# MI_04_05_Rev_2_0.net
KiCad netlist of a schematic drawn in Altium Designer
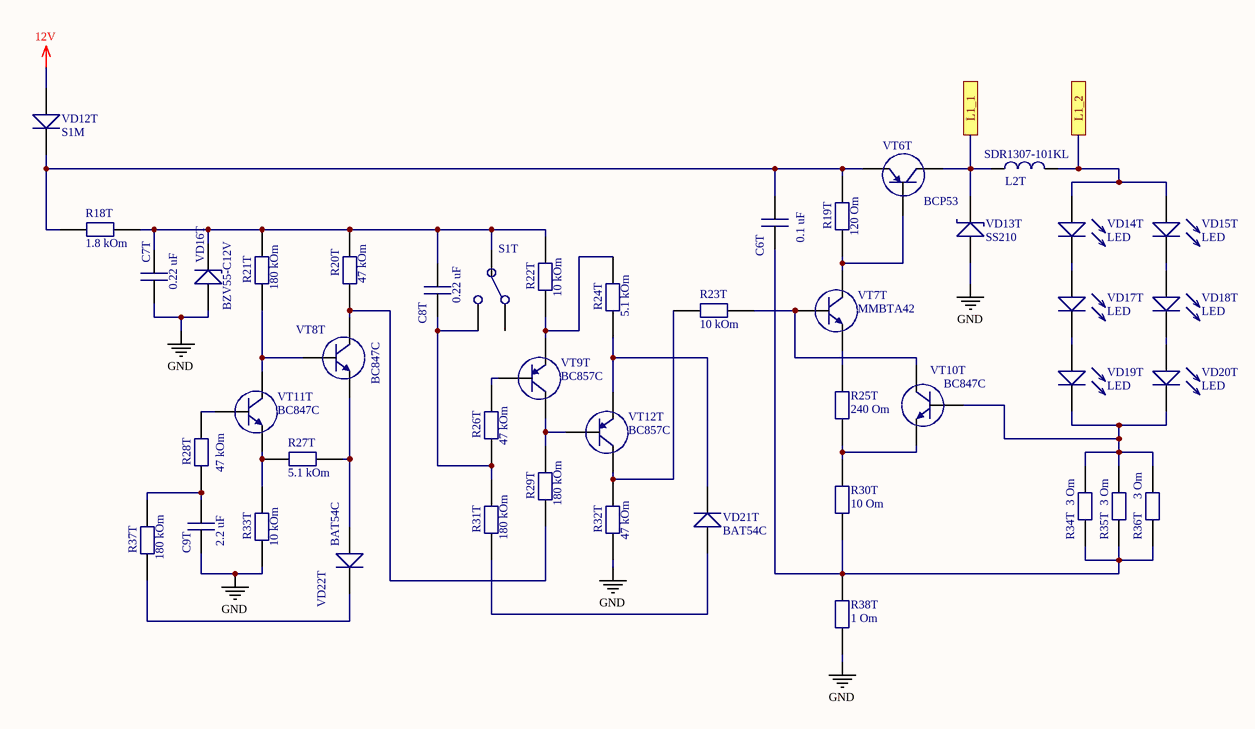
[diagram p0: MI_04_05_Rev_2_0.SchDoc]

(export (version "E")
  (design (tool "Eeschema 10.0.6"))
  (components
    (comp (ref "C6T")
      (value "0.1 uF")
      (footprint "CAP1206")
      (fields (field (name "Comment") "Capacitor"))
      (libsource (lib "my_library") (part "Capacitor"))
    )
    (comp (ref "C7T")
      (value "0.22 uF")
      (footprint "CAP1206")
      (fields (field (name "Comment") "Capacitor"))
      (libsource (lib "my_library") (part "Capacitor"))
    )
    (comp (ref "C8T")
      (value "0.22 uF")
      (footprint "CAP1206")
      (fields (field (name "Comment") "Capacitor"))
      (libsource (lib "my_library") (part "Capacitor"))
    )
    (comp (ref "C9T")
      (value "2.2 uF")
      (footprint "CAP1206")
      (fields (field (name "Comment") "Capacitor"))
      (libsource (lib "my_library") (part "Capacitor"))
    )
    (comp (ref "L2T")
      (value "SDR1307-101KL")
      (footprint "SDR1307")
      (fields (field (name "Comment") "coil"))
      (libsource (lib "my_library") (part "coil"))
    )
    (comp (ref "R18T")
      (value "1.8 kOm")
      (footprint "RES1206")
      (fields (field (name "Comment") "Resistor"))
      (libsource (lib "my_library") (part "Resistor"))
    )
    (comp (ref "R19T")
      (value "120 Om")
      (footprint "RES1206")
      (fields (field (name "Comment") "Resistor"))
      (libsource (lib "my_library") (part "Resistor"))
    )
    (comp (ref "R20T")
      (value "47 kOm")
      (footprint "RES1206")
      (fields (field (name "Comment") "Resistor"))
      (libsource (lib "my_library") (part "Resistor"))
    )
    (comp (ref "R21T")
      (value "180 kOm")
      (footprint "RES1206")
      (fields (field (name "Comment") "Resistor"))
      (libsource (lib "my_library") (part "Resistor"))
    )
    (comp (ref "R22T")
      (value "10 kOm")
      (footprint "RES1206")
      (fields (field (name "Comment") "Resistor"))
      (libsource (lib "my_library") (part "Resistor"))
    )
    (comp (ref "R23T")
      (value "10 kOm")
      (footprint "RES1206")
      (fields (field (name "Comment") "Resistor"))
      (libsource (lib "my_library") (part "Resistor"))
    )
    (comp (ref "R24T")
      (value "5.1 kOm")
      (footprint "RES1206")
      (fields (field (name "Comment") "Resistor"))
      (libsource (lib "my_library") (part "Resistor"))
    )
    (comp (ref "R25T")
      (value "240 Om")
      (footprint "RES1206")
      (fields (field (name "Comment") "Resistor"))
      (libsource (lib "my_library") (part "Resistor"))
    )
    (comp (ref "R26T")
      (value "47 kOm")
      (footprint "RES1206")
      (fields (field (name "Comment") "Resistor"))
      (libsource (lib "my_library") (part "Resistor"))
    )
    (comp (ref "R27T")
      (value "5.1 kOm")
      (footprint "RES1206")
      (fields (field (name "Comment") "Resistor"))
      (libsource (lib "my_library") (part "Resistor"))
    )
    (comp (ref "R28T")
      (value "47 kOm")
      (footprint "RES1206")
      (fields (field (name "Comment") "Resistor"))
      (libsource (lib "my_library") (part "Resistor"))
    )
    (comp (ref "R29T")
      (value "180 kOm")
      (footprint "RES1206")
      (fields (field (name "Comment") "Resistor"))
      (libsource (lib "my_library") (part "Resistor"))
    )
    (comp (ref "R30T")
      (value "10 Om")
      (footprint "RES1206")
      (fields (field (name "Comment") "Resistor"))
      (libsource (lib "my_library") (part "Resistor"))
    )
    (comp (ref "R31T")
      (value "180 kOm")
      (footprint "RES1206")
      (fields (field (name "Comment") "Resistor"))
      (libsource (lib "my_library") (part "Resistor"))
    )
    (comp (ref "R32T")
      (value "47 kOm")
      (footprint "RES1206")
      (fields (field (name "Comment") "Resistor"))
      (libsource (lib "my_library") (part "Resistor"))
    )
    (comp (ref "R33T")
      (value "10 kOm")
      (footprint "RES1206")
      (fields (field (name "Comment") "Resistor"))
      (libsource (lib "my_library") (part "Resistor"))
    )
    (comp (ref "R34T")
      (value "3 Om")
      (footprint "RES1206")
      (fields (field (name "Comment") "Resistor"))
      (libsource (lib "my_library") (part "Resistor"))
    )
    (comp (ref "R35T")
      (value "3 Om")
      (footprint "RES1206")
      (fields (field (name "Comment") "Resistor"))
      (libsource (lib "my_library") (part "Resistor"))
    )
    (comp (ref "R36T")
      (value "3 Om")
      (footprint "RES1206")
      (fields (field (name "Comment") "Resistor"))
      (libsource (lib "my_library") (part "Resistor"))
    )
    (comp (ref "R37T")
      (value "180 kOm")
      (footprint "RES1206")
      (fields (field (name "Comment") "Resistor"))
      (libsource (lib "my_library") (part "Resistor"))
    )
    (comp (ref "R38T")
      (value "1 Om")
      (footprint "RES1206")
      (fields (field (name "Comment") "Resistor"))
      (libsource (lib "my_library") (part "Resistor"))
    )
    (comp (ref "S1T")
      (value "~")
      (footprint "Solder_connector")
      (libsource (lib "my_library") (part "switch"))
    )
    (comp (ref "VD12T")
      (value "S1M")
      (footprint "SMA-F")
      (fields (field (name "Comment") "Diode"))
      (libsource (lib "my_library") (part "Diode"))
    )
    (comp (ref "VD13T")
      (value "SS210")
      (footprint "SMB1")
      (fields (field (name "Comment") "Schottky"))
      (libsource (lib "my_library") (part "Schottky"))
    )
    (comp (ref "VD14T") (value "LED") (footprint "LED_MAJAK") (libsource (lib "my_library") (part "LED")))
    (comp (ref "VD15T") (value "LED") (footprint "LED_MAJAK") (libsource (lib "my_library") (part "LED")))
    (comp (ref "VD16T")
      (value "BZV55-C12V")
      (footprint "minimelf")
      (fields (field (name "Comment") "Zenner"))
      (libsource (lib "my_library") (part "Zenner"))
    )
    (comp (ref "VD17T") (value "LED") (footprint "LED_MAJAK") (libsource (lib "my_library") (part "LED")))
    (comp (ref "VD18T") (value "LED") (footprint "LED_MAJAK") (libsource (lib "my_library") (part "LED")))
    (comp (ref "VD19T") (value "LED") (footprint "LED_MAJAK") (libsource (lib "my_library") (part "LED")))
    (comp (ref "VD20T") (value "LED") (footprint "LED_MAJAK") (libsource (lib "my_library") (part "LED")))
    (comp (ref "VD21T")
      (value "BAT54C")
      (footprint "SOT 23")
      (fields (field (name "Comment") "Diode"))
      (libsource (lib "my_library") (part "Diode"))
    )
    (comp (ref "VD22T")
      (value "BAT54C")
      (footprint "SOT 23")
      (fields (field (name "Comment") "Diode"))
      (libsource (lib "my_library") (part "Diode"))
    )
    (comp (ref "VT6T")
      (value "BCP53")
      (footprint "SOT223")
      (fields (field (name "Comment") "PNP"))
      (libsource (lib "") (part "PNP_1"))
    )
    (comp (ref "VT7T")
      (value "MMBTA42")
      (footprint "SOT 23")
      (fields (field (name "Comment") "NPN"))
      (libsource (lib "my_library") (part "NPN"))
    )
    (comp (ref "VT8T")
      (value "BC847C")
      (footprint "SOT 23")
      (fields (field (name "Comment") "NPN"))
      (libsource (lib "my_library") (part "NPN"))
    )
    (comp (ref "VT9T")
      (value "BC857C")
      (footprint "SOT 23")
      (fields (field (name "Comment") "PNP"))
      (libsource (lib "my_library") (part "PNP"))
    )
    (comp (ref "VT10T")
      (value "BC847C")
      (footprint "SOT 23")
      (fields (field (name "Comment") "NPN"))
      (libsource (lib "") (part "NPN_1"))
    )
    (comp (ref "VT11T")
      (value "BC847C")
      (footprint "SOT 23")
      (fields (field (name "Comment") "NPN"))
      (libsource (lib "my_library") (part "NPN"))
    )
    (comp (ref "VT12T")
      (value "BC857C")
      (footprint "SOT 23")
      (fields (field (name "Comment") "PNP"))
      (libsource (lib "my_library") (part "PNP"))
    )
  )
  (nets
    (net (code "1") (name "/L1_1") (class "Default")
      (node (ref "L2T") (pin "1") (pinfunction "1_1") (pintype "passive"))
      (node (ref "VD13T") (pin "1") (pinfunction "1_1") (pintype "passive"))
      (node (ref "VT6T") (pin "K") (pinfunction "K_K") (pintype "passive"))
    )
    (net (code "2") (name "/L1_2") (class "Default")
      (node (ref "L2T") (pin "2") (pinfunction "2_2") (pintype "passive"))
      (node (ref "VD14T") (pin "2") (pinfunction "2_2") (pintype "passive"))
      (node (ref "VD15T") (pin "2") (pinfunction "2_2") (pintype "passive"))
    )
    (net (code "3") (name "12V") (class "Default")
      (node (ref "VD12T") (pin "2") (pinfunction "2_2") (pintype "passive"))
    )
    (net (code "4") (name "GND") (class "Default")
      (node (ref "C7T") (pin "1") (pinfunction "1_1") (pintype "passive"))
      (node (ref "C9T") (pin "1") (pinfunction "1_1") (pintype "passive"))
      (node (ref "R32T") (pin "2") (pinfunction "2_2") (pintype "passive"))
      (node (ref "R33T") (pin "2") (pinfunction "2_2") (pintype "passive"))
      (node (ref "R38T") (pin "1") (pinfunction "1_1") (pintype "passive"))
      (node (ref "VD13T") (pin "2") (pinfunction "2_2") (pintype "passive"))
      (node (ref "VD16T") (pin "2") (pinfunction "2_2") (pintype "passive"))
    )
    (net (code "5") (name "Net-(C6T-Pad1)") (class "Default")
      (node (ref "C6T") (pin "1") (pinfunction "1_1") (pintype "passive"))
      (node (ref "R30T") (pin "1") (pinfunction "1_1") (pintype "passive"))
      (node (ref "R34T") (pin "1") (pinfunction "1_1") (pintype "passive"))
      (node (ref "R35T") (pin "1") (pinfunction "1_1") (pintype "passive"))
      (node (ref "R36T") (pin "1") (pinfunction "1_1") (pintype "passive"))
      (node (ref "R38T") (pin "2") (pinfunction "2_2") (pintype "passive"))
    )
    (net (code "6") (name "Net-(C6T-Pad2)") (class "Default")
      (node (ref "C6T") (pin "2") (pinfunction "2_2") (pintype "passive"))
      (node (ref "R18T") (pin "2") (pinfunction "2_2") (pintype "passive"))
      (node (ref "R19T") (pin "1") (pinfunction "1_1") (pintype "passive"))
      (node (ref "VD12T") (pin "1") (pinfunction "1_1") (pintype "passive"))
      (node (ref "VT6T") (pin "E") (pinfunction "E_E") (pintype "passive"))
    )
    (net (code "7") (name "Net-(C7T-Pad2)") (class "Default")
      (node (ref "C7T") (pin "2") (pinfunction "2_2") (pintype "passive"))
      (node (ref "C8T") (pin "2") (pinfunction "2_2") (pintype "passive"))
      (node (ref "R18T") (pin "1") (pinfunction "1_1") (pintype "passive"))
      (node (ref "R20T") (pin "1") (pinfunction "1_1") (pintype "passive"))
      (node (ref "R21T") (pin "1") (pinfunction "1_1") (pintype "passive"))
      (node (ref "R22T") (pin "1") (pinfunction "1_1") (pintype "passive"))
      (node (ref "S1T") (pin "1") (pinfunction "1_1") (pintype "passive"))
      (node (ref "VD16T") (pin "1") (pinfunction "1_1") (pintype "passive"))
    )
    (net (code "8") (name "Net-(C8T-Pad1)") (class "Default")
      (node (ref "C8T") (pin "1") (pinfunction "1_1") (pintype "passive"))
      (node (ref "R26T") (pin "2") (pinfunction "2_2") (pintype "passive"))
      (node (ref "R31T") (pin "1") (pinfunction "1_1") (pintype "passive"))
      (node (ref "S1T") (pin "2") (pinfunction "2_2") (pintype "passive"))
    )
    (net (code "9") (name "Net-(C9T-Pad2)") (class "Default")
      (node (ref "C9T") (pin "2") (pinfunction "2_2") (pintype "passive"))
      (node (ref "R28T") (pin "2") (pinfunction "2_2") (pintype "passive"))
      (node (ref "R37T") (pin "1") (pinfunction "1_1") (pintype "passive"))
    )
    (net (code "10") (name "Net-(R19T-Pad2)") (class "Default")
      (node (ref "R19T") (pin "2") (pinfunction "2_2") (pintype "passive"))
      (node (ref "VT6T") (pin "B") (pinfunction "B_B") (pintype "passive"))
      (node (ref "VT7T") (pin "K") (pinfunction "K_K") (pintype "passive"))
    )
    (net (code "11") (name "Net-(R20T-Pad2)") (class "Default")
      (node (ref "R20T") (pin "2") (pinfunction "2_2") (pintype "passive"))
      (node (ref "R29T") (pin "2") (pinfunction "2_2") (pintype "passive"))
      (node (ref "VT8T") (pin "K") (pinfunction "K_K") (pintype "passive"))
    )
    (net (code "12") (name "Net-(R21T-Pad2)") (class "Default")
      (node (ref "R21T") (pin "2") (pinfunction "2_2") (pintype "passive"))
      (node (ref "VT11T") (pin "K") (pinfunction "K_K") (pintype "passive"))
      (node (ref "VT8T") (pin "B") (pinfunction "B_B") (pintype "passive"))
    )
    (net (code "13") (name "Net-(R22T-Pad2)") (class "Default")
      (node (ref "R22T") (pin "2") (pinfunction "2_2") (pintype "passive"))
      (node (ref "R24T") (pin "1") (pinfunction "1_1") (pintype "passive"))
      (node (ref "VT9T") (pin "E") (pinfunction "E_E") (pintype "passive"))
    )
    (net (code "14") (name "Net-(R23T-Pad1)") (class "Default")
      (node (ref "R23T") (pin "1") (pinfunction "1_1") (pintype "passive"))
      (node (ref "R32T") (pin "1") (pinfunction "1_1") (pintype "passive"))
      (node (ref "VT12T") (pin "K") (pinfunction "K_K") (pintype "passive"))
    )
    (net (code "15") (name "Net-(R23T-Pad2)") (class "Default")
      (node (ref "R23T") (pin "2") (pinfunction "2_2") (pintype "passive"))
      (node (ref "VT10T") (pin "K") (pinfunction "K_K") (pintype "passive"))
      (node (ref "VT7T") (pin "B") (pinfunction "B_B") (pintype "passive"))
    )
    (net (code "16") (name "Net-(R24T-Pad2)") (class "Default")
      (node (ref "R24T") (pin "2") (pinfunction "2_2") (pintype "passive"))
      (node (ref "VD21T") (pin "1") (pinfunction "1_1") (pintype "passive"))
      (node (ref "VT12T") (pin "E") (pinfunction "E_E") (pintype "passive"))
    )
    (net (code "17") (name "Net-(R25T-Pad1)") (class "Default")
      (node (ref "R25T") (pin "1") (pinfunction "1_1") (pintype "passive"))
      (node (ref "R30T") (pin "2") (pinfunction "2_2") (pintype "passive"))
      (node (ref "VT10T") (pin "E") (pinfunction "E_E") (pintype "passive"))
    )
    (net (code "18") (name "Net-(R25T-Pad2)") (class "Default")
      (node (ref "R25T") (pin "2") (pinfunction "2_2") (pintype "passive"))
      (node (ref "VT7T") (pin "E") (pinfunction "E_E") (pintype "passive"))
    )
    (net (code "19") (name "Net-(R26T-Pad1)") (class "Default")
      (node (ref "R26T") (pin "1") (pinfunction "1_1") (pintype "passive"))
      (node (ref "VT9T") (pin "B") (pinfunction "B_B") (pintype "passive"))
    )
    (net (code "20") (name "Net-(R27T-Pad1)") (class "Default")
      (node (ref "R27T") (pin "1") (pinfunction "1_1") (pintype "passive"))
      (node (ref "VD22T") (pin "2") (pinfunction "2_2") (pintype "passive"))
      (node (ref "VT8T") (pin "E") (pinfunction "E_E") (pintype "passive"))
    )
    (net (code "21") (name "Net-(R27T-Pad2)") (class "Default")
      (node (ref "R27T") (pin "2") (pinfunction "2_2") (pintype "passive"))
      (node (ref "R33T") (pin "1") (pinfunction "1_1") (pintype "passive"))
      (node (ref "VT11T") (pin "E") (pinfunction "E_E") (pintype "passive"))
    )
    (net (code "22") (name "Net-(R28T-Pad1)") (class "Default")
      (node (ref "R28T") (pin "1") (pinfunction "1_1") (pintype "passive"))
      (node (ref "VT11T") (pin "B") (pinfunction "B_B") (pintype "passive"))
    )
    (net (code "23") (name "Net-(R29T-Pad1)") (class "Default")
      (node (ref "R29T") (pin "1") (pinfunction "1_1") (pintype "passive"))
      (node (ref "VT12T") (pin "B") (pinfunction "B_B") (pintype "passive"))
      (node (ref "VT9T") (pin "K") (pinfunction "K_K") (pintype "passive"))
    )
    (net (code "24") (name "Net-(R31T-Pad2)") (class "Default")
      (node (ref "R31T") (pin "2") (pinfunction "2_2") (pintype "passive"))
      (node (ref "VD21T") (pin "2") (pinfunction "2_2") (pintype "passive"))
    )
    (net (code "25") (name "Net-(R34T-Pad2)") (class "Default")
      (node (ref "R34T") (pin "2") (pinfunction "2_2") (pintype "passive"))
      (node (ref "R35T") (pin "2") (pinfunction "2_2") (pintype "passive"))
      (node (ref "R36T") (pin "2") (pinfunction "2_2") (pintype "passive"))
      (node (ref "VD19T") (pin "1") (pinfunction "1_1") (pintype "passive"))
      (node (ref "VD20T") (pin "1") (pinfunction "1_1") (pintype "passive"))
      (node (ref "VT10T") (pin "B") (pinfunction "B_B") (pintype "passive"))
    )
    (net (code "26") (name "Net-(R37T-Pad2)") (class "Default")
      (node (ref "R37T") (pin "2") (pinfunction "2_2") (pintype "passive"))
      (node (ref "VD22T") (pin "1") (pinfunction "1_1") (pintype "passive"))
    )
    (net (code "27") (name "Net-(VD14T-Pad1)") (class "Default")
      (node (ref "VD14T") (pin "1") (pinfunction "1_1") (pintype "passive"))
      (node (ref "VD17T") (pin "2") (pinfunction "2_2") (pintype "passive"))
    )
    (net (code "28") (name "Net-(VD15T-Pad1)") (class "Default")
      (node (ref "VD15T") (pin "1") (pinfunction "1_1") (pintype "passive"))
      (node (ref "VD18T") (pin "2") (pinfunction "2_2") (pintype "passive"))
    )
    (net (code "29") (name "Net-(VD17T-Pad1)") (class "Default")
      (node (ref "VD17T") (pin "1") (pinfunction "1_1") (pintype "passive"))
      (node (ref "VD19T") (pin "2") (pinfunction "2_2") (pintype "passive"))
    )
    (net (code "30") (name "Net-(VD18T-Pad1)") (class "Default")
      (node (ref "VD18T") (pin "1") (pinfunction "1_1") (pintype "passive"))
      (node (ref "VD20T") (pin "2") (pinfunction "2_2") (pintype "passive"))
    )
    (net (code "31") (name "unconnected-(S1T-Pad3)") (class "Default")
      (node (ref "S1T") (pin "3") (pinfunction "3_3") (pintype "passive"))
    )
  )
)
